# UsbDmx.net
KiCad netlist of a schematic drawn in EAGLE
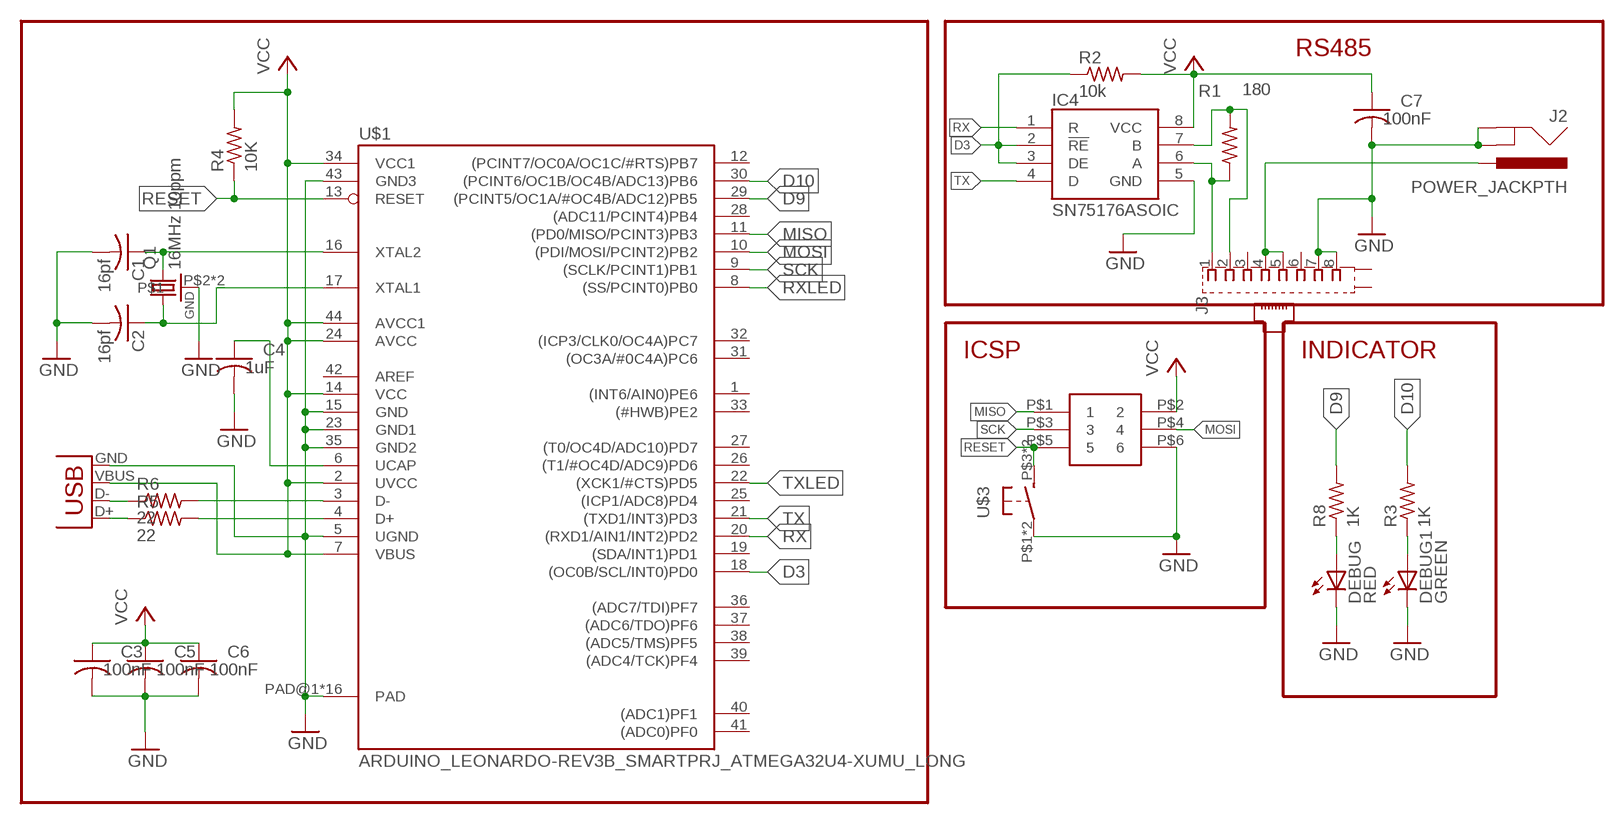
[diagram p0: schematic, sheet 1]

(export (version "E")
  (design (tool "Eeschema 10.0.6"))
  (components
    (comp (ref "C1")
      (value "16pf")
      (footprint "eagle-import:C0603")
      (libsource (lib "eagle-import") (part "C-USC0603"))
    )
    (comp (ref "C2")
      (value "16pf")
      (footprint "eagle-import:C0603")
      (libsource (lib "eagle-import") (part "C-USC0603"))
    )
    (comp (ref "C3")
      (value "100nF")
      (footprint "eagle-import:C0603")
      (libsource (lib "eagle-import") (part "C-USC0603"))
    )
    (comp (ref "C4")
      (value "1uF")
      (footprint "eagle-import:C0603")
      (libsource (lib "eagle-import") (part "C-USC0603"))
    )
    (comp (ref "C5")
      (value "100nF")
      (footprint "eagle-import:C0603")
      (libsource (lib "eagle-import") (part "C-USC0603"))
    )
    (comp (ref "C6")
      (value "100nF")
      (footprint "eagle-import:C0603")
      (libsource (lib "eagle-import") (part "C-USC0603"))
    )
    (comp (ref "C7")
      (value "100nF")
      (footprint "eagle-import:C0603")
      (libsource (lib "eagle-import") (part "C-USC0603"))
    )
    (comp (ref "DEBUG")
      (value "RED")
      (footprint "eagle-import:LED-0805")
      (libsource (lib "eagle-import") (part "LED0805"))
    )
    (comp (ref "DEBUG1")
      (value "GREEN")
      (footprint "eagle-import:LED-0805")
      (libsource (lib "eagle-import") (part "LED0805"))
    )
    (comp (ref "IC4")
      (value "SN75176ASOIC")
      (footprint "eagle-import:SO08")
      (libsource (lib "eagle-import") (part "SN75176ASOIC"))
    )
    (comp (ref "J2")
      (value "POWER_JACKPTH")
      (footprint "eagle-import:POWER_JACK_PTH")
      (libsource (lib "eagle-import") (part "POWER_JACKPTH"))
    )
    (comp (ref "J3")
      (value "555153-1")
      (footprint "eagle-import:555153-1")
      (libsource (lib "eagle-import") (part "555153-1"))
    )
    (comp (ref "Q1")
      (value "16MHz 10ppm")
      (footprint "eagle-import:CRSYTAL_2520")
      (libsource (lib "eagle-import") (part "CRYSTAL_4PAD2520"))
    )
    (comp (ref "R1")
      (value "180")
      (footprint "eagle-import:R0603")
      (libsource (lib "eagle-import") (part "R-US_R0603"))
    )
    (comp (ref "R2")
      (value "10k")
      (footprint "eagle-import:R0603")
      (libsource (lib "eagle-import") (part "R-US_R0603"))
    )
    (comp (ref "R3")
      (value "1K")
      (footprint "eagle-import:R0603")
      (libsource (lib "eagle-import") (part "R-US_R0603"))
    )
    (comp (ref "R4")
      (value "10K")
      (footprint "eagle-import:R0603")
      (libsource (lib "eagle-import") (part "R-US_R0603"))
    )
    (comp (ref "R5")
      (value "22")
      (footprint "eagle-import:R0603")
      (libsource (lib "eagle-import") (part "R-US_R0603"))
    )
    (comp (ref "R6")
      (value "22")
      (footprint "eagle-import:R0603")
      (libsource (lib "eagle-import") (part "R-US_R0603"))
    )
    (comp (ref "R8")
      (value "1K")
      (footprint "eagle-import:R0603")
      (libsource (lib "eagle-import") (part "R-US_R0603"))
    )
    (comp (ref "U$1")
      (value "ARDUINO_LEONARDO-REV3B_SMARTPRJ_ATMEGA32U4-XUMU_LONG")
      (footprint "eagle-import:QFN44ML7X7_LONGLEADS")
      (libsource (lib "eagle-import") (part "ARDUINO_LEONARDO-REV3B_SMARTPRJ_ATMEGA32U4-XUMU_LONG"))
    )
    (comp (ref "U$2")
      (value "2X3HEADER")
      (footprint "eagle-import:2X3HEADER")
      (libsource (lib "eagle-import") (part "2X3HEADER"))
    )
    (comp (ref "U$3")
      (value "BUTTON_MOMENTARY")
      (footprint "eagle-import:BUTTON_MOMENTARY_KMR211G")
      (libsource (lib "eagle-import") (part "BUTTON_MOMENTARY"))
    )
    (comp (ref "X1")
      (value "USBPTH")
      (footprint "eagle-import:USB-B-PTH")
      (libsource (lib "eagle-import") (part "USBPTH"))
    )
  )
  (nets
    (net (code "1") (name "/AREF") (class "Default")
      (node (ref "U$1") (pin "42") (pinfunction "AREF_42") (pintype "power_in"))
    )
    (net (code "2") (name "D3") (class "Default")
      (node (ref "IC4") (pin "2") (pinfunction "~{RE}_2") (pintype "bidirectional"))
      (node (ref "IC4") (pin "3") (pinfunction "DE_3") (pintype "bidirectional"))
      (node (ref "R2") (pin "1") (pinfunction "1_1") (pintype "passive"))
      (node (ref "U$1") (pin "18") (pinfunction "(OC0B/SCL/INT0)PD0_18") (pintype "bidirectional"))
    )
    (net (code "3") (name "D9") (class "Default")
      (node (ref "R8") (pin "2") (pinfunction "2_2") (pintype "passive"))
      (node (ref "U$1") (pin "29") (pinfunction "(PCINT5/OC1A/#OC4B/ADC12)PB5_29") (pintype "bidirectional"))
    )
    (net (code "4") (name "D10") (class "Default")
      (node (ref "R3") (pin "2") (pinfunction "2_2") (pintype "passive"))
      (node (ref "U$1") (pin "30") (pinfunction "(PCINT6/OC1B/OC4B/ADC13)PB6_30") (pintype "bidirectional"))
    )
    (net (code "5") (name "GND") (class "Default")
      (node (ref "C1") (pin "2") (pinfunction "2_2") (pintype "passive"))
      (node (ref "C2") (pin "2") (pinfunction "2_2") (pintype "passive"))
      (node (ref "C3") (pin "2") (pinfunction "2_2") (pintype "passive"))
      (node (ref "C4") (pin "2") (pinfunction "2_2") (pintype "passive"))
      (node (ref "C5") (pin "2") (pinfunction "2_2") (pintype "passive"))
      (node (ref "C6") (pin "2") (pinfunction "2_2") (pintype "passive"))
      (node (ref "C7") (pin "2") (pinfunction "2_2") (pintype "passive"))
      (node (ref "DEBUG") (pin "C") (pinfunction "C_C") (pintype "passive"))
      (node (ref "DEBUG1") (pin "C") (pinfunction "C_C") (pintype "passive"))
      (node (ref "IC4") (pin "5") (pinfunction "GND_5") (pintype "bidirectional"))
      (node (ref "J2") (pin "GND") (pinfunction "GND_GND") (pintype "bidirectional"))
      (node (ref "J2") (pin "GNDBREAK") (pinfunction "GNDBREAK_GNDBREAK") (pintype "bidirectional"))
      (node (ref "J3") (pin "7") (pinfunction "7_7") (pintype "passive"))
      (node (ref "J3") (pin "8") (pinfunction "8_8") (pintype "passive"))
      (node (ref "Q1") (pin "P$2") (pinfunction "P$1_P$2") (pintype "bidirectional"))
      (node (ref "Q1") (pin "P$4") (pinfunction "P$1_P$4") (pintype "bidirectional"))
      (node (ref "U$1") (pin "15") (pinfunction "GND_15") (pintype "power_in"))
      (node (ref "U$1") (pin "23") (pinfunction "GND1_23") (pintype "power_in"))
      (node (ref "U$1") (pin "35") (pinfunction "GND2_35") (pintype "power_in"))
      (node (ref "U$1") (pin "43") (pinfunction "GND3_43") (pintype "power_in"))
      (node (ref "U$1") (pin "5") (pinfunction "UGND_5") (pintype "power_in"))
      (node (ref "U$1") (pin "PAD@1") (pinfunction "PAD_PAD@1") (pintype "power_in"))
      (node (ref "U$1") (pin "PAD@10") (pinfunction "PAD_PAD@10") (pintype "power_in"))
      (node (ref "U$1") (pin "PAD@11") (pinfunction "PAD_PAD@11") (pintype "power_in"))
      (node (ref "U$1") (pin "PAD@12") (pinfunction "PAD_PAD@12") (pintype "power_in"))
      (node (ref "U$1") (pin "PAD@13") (pinfunction "PAD_PAD@13") (pintype "power_in"))
      (node (ref "U$1") (pin "PAD@14") (pinfunction "PAD_PAD@14") (pintype "power_in"))
      (node (ref "U$1") (pin "PAD@15") (pinfunction "PAD_PAD@15") (pintype "power_in"))
      (node (ref "U$1") (pin "PAD@16") (pinfunction "PAD_PAD@16") (pintype "power_in"))
      (node (ref "U$1") (pin "PAD@2") (pinfunction "PAD_PAD@2") (pintype "power_in"))
      (node (ref "U$1") (pin "PAD@3") (pinfunction "PAD_PAD@3") (pintype "power_in"))
      (node (ref "U$1") (pin "PAD@4") (pinfunction "PAD_PAD@4") (pintype "power_in"))
      (node (ref "U$1") (pin "PAD@5") (pinfunction "PAD_PAD@5") (pintype "power_in"))
      (node (ref "U$1") (pin "PAD@6") (pinfunction "PAD_PAD@6") (pintype "power_in"))
      (node (ref "U$1") (pin "PAD@7") (pinfunction "PAD_PAD@7") (pintype "power_in"))
      (node (ref "U$1") (pin "PAD@8") (pinfunction "PAD_PAD@8") (pintype "power_in"))
      (node (ref "U$1") (pin "PAD@9") (pinfunction "PAD_PAD@9") (pintype "power_in"))
      (node (ref "U$2") (pin "P$6") (pinfunction "6_P$6") (pintype "bidirectional"))
      (node (ref "U$3") (pin "P$1") (pinfunction "P_P$1") (pintype "passive"))
      (node (ref "U$3") (pin "P$2") (pinfunction "P_P$2") (pintype "passive"))
      (node (ref "X1") (pin "GND") (pinfunction "GND_GND") (pintype "bidirectional"))
    )
    (net (code "6") (name "MISO") (class "Default")
      (node (ref "U$1") (pin "11") (pinfunction "(PD0/MISO/PCINT3)PB3_11") (pintype "bidirectional"))
      (node (ref "U$2") (pin "P$1") (pinfunction "1_P$1") (pintype "bidirectional"))
    )
    (net (code "7") (name "MOSI") (class "Default")
      (node (ref "U$1") (pin "10") (pinfunction "(PDI/MOSI/PCINT2)PB2_10") (pintype "bidirectional"))
      (node (ref "U$2") (pin "P$4") (pinfunction "4_P$4") (pintype "bidirectional"))
    )
    (net (code "8") (name "Net-(DEBUG-PadA)") (class "Default")
      (node (ref "DEBUG") (pin "A") (pinfunction "A_A") (pintype "passive"))
      (node (ref "R8") (pin "1") (pinfunction "1_1") (pintype "passive"))
    )
    (net (code "9") (name "Net-(DEBUG1-PadA)") (class "Default")
      (node (ref "DEBUG1") (pin "A") (pinfunction "A_A") (pintype "passive"))
      (node (ref "R3") (pin "1") (pinfunction "1_1") (pintype "passive"))
    )
    (net (code "10") (name "Net-(IC4-A)") (class "Default")
      (node (ref "IC4") (pin "6") (pinfunction "A_6") (pintype "bidirectional"))
      (node (ref "J3") (pin "1") (pinfunction "1_1") (pintype "passive"))
      (node (ref "R1") (pin "1") (pinfunction "1_1") (pintype "passive"))
    )
    (net (code "11") (name "Net-(IC4-B)") (class "Default")
      (node (ref "IC4") (pin "7") (pinfunction "B_7") (pintype "bidirectional"))
      (node (ref "J3") (pin "2") (pinfunction "2_2") (pintype "passive"))
      (node (ref "R1") (pin "2") (pinfunction "2_2") (pintype "passive"))
    )
    (net (code "12") (name "Net-(J2-PadPWR)") (class "Default")
      (node (ref "J2") (pin "PWR") (pinfunction "PWR_PWR") (pintype "bidirectional"))
      (node (ref "J3") (pin "4") (pinfunction "4_4") (pintype "passive"))
      (node (ref "J3") (pin "5") (pinfunction "5_5") (pintype "passive"))
    )
    (net (code "13") (name "Net-(Q1-1)") (class "Default")
      (node (ref "C2") (pin "1") (pinfunction "1_1") (pintype "passive"))
      (node (ref "Q1") (pin "P$1") (pinfunction "1_P$1") (pintype "passive"))
      (node (ref "U$1") (pin "17") (pinfunction "XTAL1_17") (pintype "bidirectional"))
    )
    (net (code "14") (name "Net-(Q1-2)") (class "Default")
      (node (ref "C1") (pin "1") (pinfunction "1_1") (pintype "passive"))
      (node (ref "Q1") (pin "P$3") (pinfunction "2_P$3") (pintype "passive"))
      (node (ref "U$1") (pin "16") (pinfunction "XTAL2_16") (pintype "bidirectional"))
    )
    (net (code "15") (name "Net-(R5-Pad1)") (class "Default")
      (node (ref "R5") (pin "1") (pinfunction "1_1") (pintype "passive"))
      (node (ref "X1") (pin "D+") (pinfunction "D+_D+") (pintype "bidirectional"))
    )
    (net (code "16") (name "Net-(R6-Pad1)") (class "Default")
      (node (ref "R6") (pin "1") (pinfunction "1_1") (pintype "passive"))
      (node (ref "X1") (pin "D-") (pinfunction "D-_D-") (pintype "bidirectional"))
    )
    (net (code "17") (name "Net-(U$1-D+)") (class "Default")
      (node (ref "R5") (pin "2") (pinfunction "2_2") (pintype "passive"))
      (node (ref "U$1") (pin "4") (pinfunction "D+_4") (pintype "bidirectional"))
    )
    (net (code "18") (name "Net-(U$1-D-)") (class "Default")
      (node (ref "R6") (pin "2") (pinfunction "2_2") (pintype "passive"))
      (node (ref "U$1") (pin "3") (pinfunction "D-_3") (pintype "bidirectional"))
    )
    (net (code "19") (name "Net-(U$1-UCAP)") (class "Default")
      (node (ref "C4") (pin "1") (pinfunction "1_1") (pintype "passive"))
      (node (ref "U$1") (pin "6") (pinfunction "UCAP_6") (pintype "passive"))
    )
    (net (code "20") (name "RESET") (class "Default")
      (node (ref "R4") (pin "1") (pinfunction "1_1") (pintype "passive"))
      (node (ref "U$1") (pin "13") (pinfunction "RESET_13") (pintype "input"))
      (node (ref "U$2") (pin "P$5") (pinfunction "5_P$5") (pintype "bidirectional"))
      (node (ref "U$3") (pin "P$3") (pinfunction "S_P$3") (pintype "passive"))
      (node (ref "U$3") (pin "P$4") (pinfunction "S_P$4") (pintype "passive"))
    )
    (net (code "21") (name "RX") (class "Default")
      (node (ref "IC4") (pin "1") (pinfunction "R_1") (pintype "bidirectional"))
      (node (ref "U$1") (pin "20") (pinfunction "(RXD1/AIN1/INT2)PD2_20") (pintype "bidirectional"))
    )
    (net (code "22") (name "RXLED") (class "Default")
      (node (ref "U$1") (pin "8") (pinfunction "(SS/PCINT0)PB0_8") (pintype "bidirectional"))
    )
    (net (code "23") (name "SCK") (class "Default")
      (node (ref "U$1") (pin "9") (pinfunction "(SCLK/PCINT1)PB1_9") (pintype "bidirectional"))
      (node (ref "U$2") (pin "P$3") (pinfunction "3_P$3") (pintype "bidirectional"))
    )
    (net (code "24") (name "TX") (class "Default")
      (node (ref "IC4") (pin "4") (pinfunction "D_4") (pintype "bidirectional"))
      (node (ref "U$1") (pin "21") (pinfunction "(TXD1/INT3)PD3_21") (pintype "bidirectional"))
    )
    (net (code "25") (name "TXLED") (class "Default")
      (node (ref "U$1") (pin "22") (pinfunction "(XCK1/#CTS)PD5_22") (pintype "bidirectional"))
    )
    (net (code "26") (name "VCC") (class "Default")
      (node (ref "C3") (pin "1") (pinfunction "1_1") (pintype "passive"))
      (node (ref "C5") (pin "1") (pinfunction "1_1") (pintype "passive"))
      (node (ref "C6") (pin "1") (pinfunction "1_1") (pintype "passive"))
      (node (ref "C7") (pin "1") (pinfunction "1_1") (pintype "passive"))
      (node (ref "IC4") (pin "8") (pinfunction "VCC_8") (pintype "bidirectional"))
      (node (ref "R2") (pin "2") (pinfunction "2_2") (pintype "passive"))
      (node (ref "R4") (pin "2") (pinfunction "2_2") (pintype "passive"))
      (node (ref "U$1") (pin "14") (pinfunction "VCC_14") (pintype "power_in"))
      (node (ref "U$1") (pin "2") (pinfunction "UVCC_2") (pintype "power_in"))
      (node (ref "U$1") (pin "24") (pinfunction "AVCC_24") (pintype "power_in"))
      (node (ref "U$1") (pin "34") (pinfunction "VCC1_34") (pintype "power_in"))
      (node (ref "U$1") (pin "44") (pinfunction "AVCC1_44") (pintype "power_in"))
      (node (ref "U$1") (pin "7") (pinfunction "VBUS_7") (pintype "input"))
      (node (ref "U$2") (pin "P$2") (pinfunction "2_P$2") (pintype "bidirectional"))
      (node (ref "X1") (pin "VBUS") (pinfunction "VBUS_VBUS") (pintype "bidirectional"))
    )
    (net (code "27") (name "unconnected-(J3-Pad3)") (class "Default")
      (node (ref "J3") (pin "3") (pinfunction "3_3") (pintype "passive"))
    )
    (net (code "28") (name "unconnected-(J3-Pad6)") (class "Default")
      (node (ref "J3") (pin "6") (pinfunction "6_6") (pintype "passive"))
    )
    (net (code "29") (name "unconnected-(J3-S1-PadG1)") (class "Default")
      (node (ref "J3") (pin "G1") (pinfunction "S1_G1") (pintype "passive"))
    )
    (net (code "30") (name "unconnected-(J3-S2-PadG2)") (class "Default")
      (node (ref "J3") (pin "G2") (pinfunction "S2_G2") (pintype "passive"))
    )
    (net (code "31") (name "unconnected-(U$1-(#HWB)PE2-Pad33)") (class "Default")
      (node (ref "U$1") (pin "33") (pinfunction "(#HWB)PE2_33") (pintype "bidirectional"))
    )
    (net (code "32") (name "unconnected-(U$1-(ADC0)PF0-Pad41)") (class "Default")
      (node (ref "U$1") (pin "41") (pinfunction "(ADC0)PF0_41") (pintype "bidirectional"))
    )
    (net (code "33") (name "unconnected-(U$1-(ADC1)PF1-Pad40)") (class "Default")
      (node (ref "U$1") (pin "40") (pinfunction "(ADC1)PF1_40") (pintype "bidirectional"))
    )
    (net (code "34") (name "unconnected-(U$1-(ADC4{slash}TCK)PF4-Pad39)") (class "Default")
      (node (ref "U$1") (pin "39") (pinfunction "(ADC4/TCK)PF4_39") (pintype "bidirectional"))
    )
    (net (code "35") (name "unconnected-(U$1-(ADC5{slash}TMS)PF5-Pad38)") (class "Default")
      (node (ref "U$1") (pin "38") (pinfunction "(ADC5/TMS)PF5_38") (pintype "bidirectional"))
    )
    (net (code "36") (name "unconnected-(U$1-(ADC6{slash}TDO)PF6-Pad37)") (class "Default")
      (node (ref "U$1") (pin "37") (pinfunction "(ADC6/TDO)PF6_37") (pintype "bidirectional"))
    )
    (net (code "37") (name "unconnected-(U$1-(ADC7{slash}TDI)PF7-Pad36)") (class "Default")
      (node (ref "U$1") (pin "36") (pinfunction "(ADC7/TDI)PF7_36") (pintype "bidirectional"))
    )
    (net (code "38") (name "unconnected-(U$1-(ADC11{slash}PCINT4)PB4-Pad28)") (class "Default")
      (node (ref "U$1") (pin "28") (pinfunction "(ADC11/PCINT4)PB4_28") (pintype "bidirectional"))
    )
    (net (code "39") (name "unconnected-(U$1-(ICP1{slash}ADC8)PD4-Pad25)") (class "Default")
      (node (ref "U$1") (pin "25") (pinfunction "(ICP1/ADC8)PD4_25") (pintype "bidirectional"))
    )
    (net (code "40") (name "unconnected-(U$1-(ICP3{slash}CLK0{slash}OC4A)PC7-Pad32)") (class "Default")
      (node (ref "U$1") (pin "32") (pinfunction "(ICP3/CLK0/OC4A)PC7_32") (pintype "bidirectional"))
    )
    (net (code "41") (name "unconnected-(U$1-(INT6{slash}AIN0)PE6-Pad1)") (class "Default")
      (node (ref "U$1") (pin "1") (pinfunction "(INT6/AIN0)PE6_1") (pintype "bidirectional"))
    )
    (net (code "42") (name "unconnected-(U$1-(OC3A{slash}#0C4A)PC6-Pad31)") (class "Default")
      (node (ref "U$1") (pin "31") (pinfunction "(OC3A/#0C4A)PC6_31") (pintype "bidirectional"))
    )
    (net (code "43") (name "unconnected-(U$1-(PCINT7{slash}OC0A{slash}OC1C{slash}#RTS)PB7-Pad12)") (class "Default")
      (node (ref "U$1") (pin "12") (pinfunction "(PCINT7/OC0A/OC1C/#RTS)PB7_12") (pintype "bidirectional"))
    )
    (net (code "44") (name "unconnected-(U$1-(SDA{slash}INT1)PD1-Pad19)") (class "Default")
      (node (ref "U$1") (pin "19") (pinfunction "(SDA/INT1)PD1_19") (pintype "bidirectional"))
    )
    (net (code "45") (name "unconnected-(U$1-(T0{slash}OC4D{slash}ADC10)PD7-Pad27)") (class "Default")
      (node (ref "U$1") (pin "27") (pinfunction "(T0/OC4D/ADC10)PD7_27") (pintype "bidirectional"))
    )
    (net (code "46") (name "unconnected-(U$1-(T1{slash}#OC4D{slash}ADC9)PD6-Pad26)") (class "Default")
      (node (ref "U$1") (pin "26") (pinfunction "(T1/#OC4D/ADC9)PD6_26") (pintype "bidirectional"))
    )
  )
)
